# spb_sample_sch.net
KiCad netlist of a schematic drawn in Altium Designer
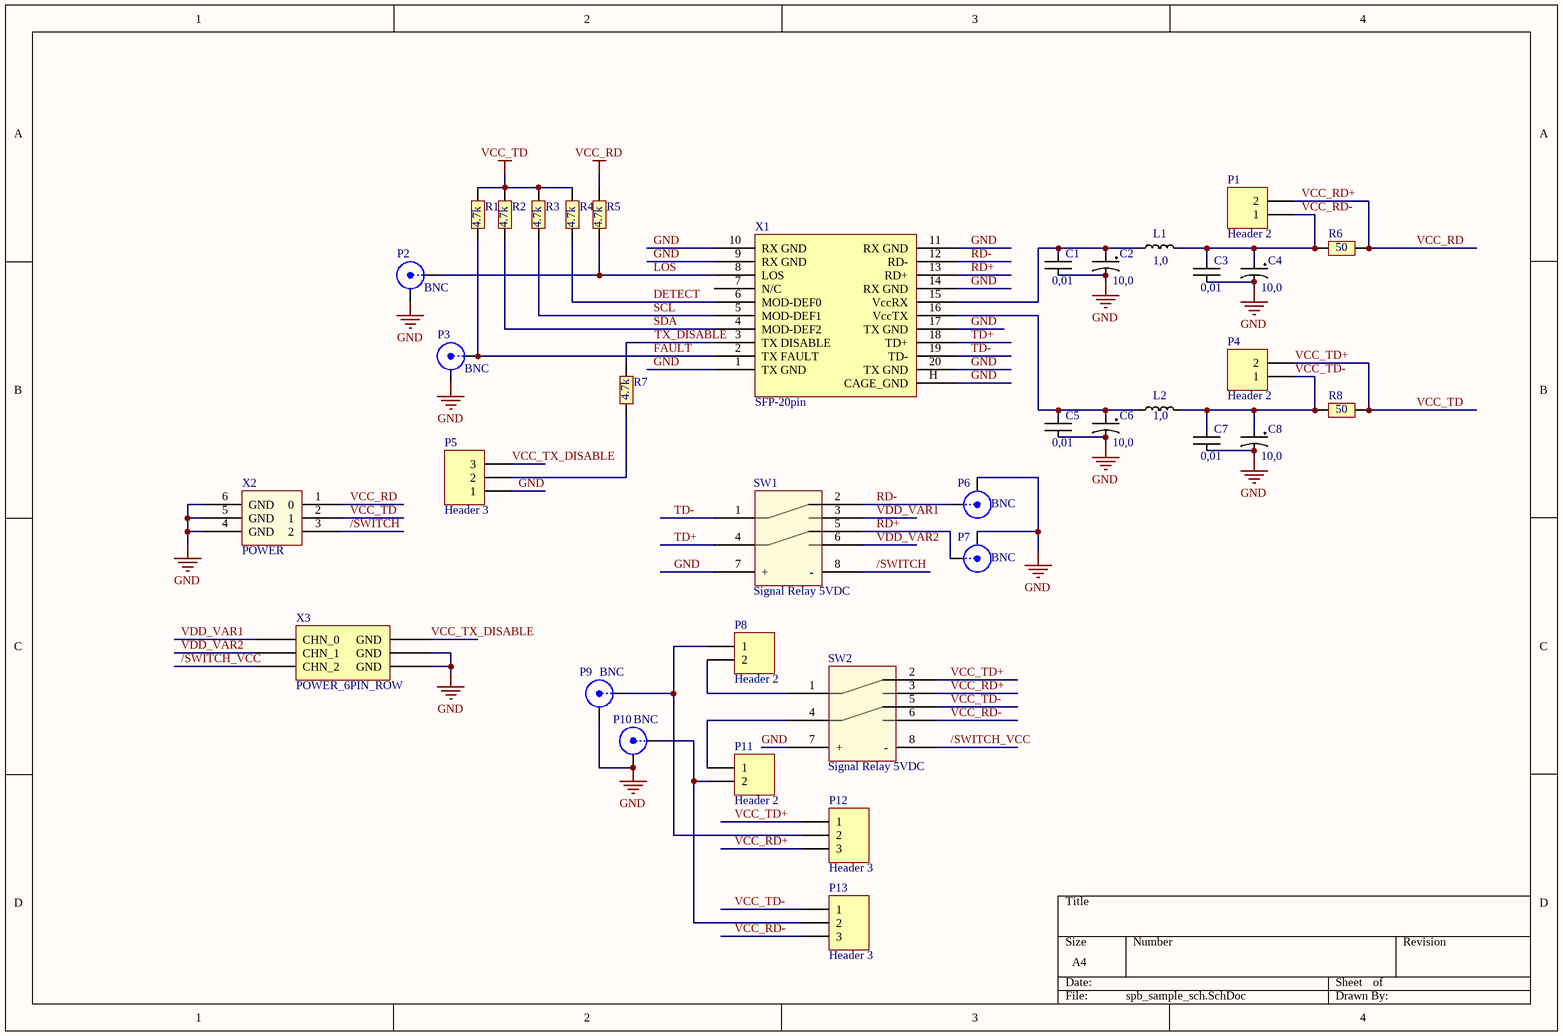
[diagram p0: spb_sample_sch.SchDoc]

(export (version "E")
  (design (tool "Eeschema 10.0.6"))
  (components
    (comp (ref "C1")
      (value "0,01")
      (footprint "0805")
      (description "0805")
      (libsource (lib "MIT_Schlib") (part "CAP_SMALL"))
    )
    (comp (ref "C2")
      (value "10,0")
      (footprint "TYPE_C")
      (description "SMD")
      (libsource (lib "MIT_Schlib") (part "CAP_TANT"))
    )
    (comp (ref "C3")
      (value "0,01")
      (footprint "0805")
      (description "0805")
      (libsource (lib "MIT_Schlib") (part "CAP_SMALL"))
    )
    (comp (ref "C4")
      (value "10,0")
      (footprint "TYPE_C")
      (description "SMD")
      (libsource (lib "MIT_Schlib") (part "CAP_TANT"))
    )
    (comp (ref "C5")
      (value "0,01")
      (footprint "0805")
      (description "0805")
      (libsource (lib "MIT_Schlib") (part "CAP_SMALL"))
    )
    (comp (ref "C6")
      (value "10,0")
      (footprint "TYPE_C")
      (description "SMD")
      (libsource (lib "MIT_Schlib") (part "CAP_TANT"))
    )
    (comp (ref "C7")
      (value "0,01")
      (footprint "0805")
      (description "0805")
      (libsource (lib "MIT_Schlib") (part "CAP_SMALL"))
    )
    (comp (ref "C8")
      (value "10,0")
      (footprint "TYPE_C")
      (description "SMD")
      (libsource (lib "MIT_Schlib") (part "CAP_TANT"))
    )
    (comp (ref "L1")
      (value "1,0")
      (footprint "0805")
      (description "0805")
      (libsource (lib "MIT_Schlib") (part "INDUCT"))
    )
    (comp (ref "L2")
      (value "1,0")
      (footprint "0805")
      (description "0805")
      (libsource (lib "MIT_Schlib") (part "INDUCT"))
    )
    (comp (ref "P1")
      (value "Header 2")
      (footprint "HDR1X2")
      (description "Header, 2-Pin")
      (fields (field (name "PUBLISHER") "Altium Limited"))
      (libsource (lib "Miscellaneous Connectors") (part "Header 2"))
    )
    (comp (ref "P2")
      (value "BNC")
      (footprint "BNC_RA CON")
      (description "BNC Elbow Connector")
      (fields (field (name "PUBLISHER") "Altium Limited"))
      (libsource (lib "Miscellaneous Connectors") (part "BNC"))
    )
    (comp (ref "P3")
      (value "BNC")
      (footprint "BNC_RA CON")
      (description "BNC Elbow Connector")
      (fields (field (name "PUBLISHER") "Altium Limited"))
      (libsource (lib "Miscellaneous Connectors") (part "BNC"))
    )
    (comp (ref "P4")
      (value "Header 2")
      (footprint "HDR1X2")
      (description "Header, 2-Pin")
      (fields (field (name "PUBLISHER") "Altium Limited"))
      (libsource (lib "Miscellaneous Connectors") (part "Header 2"))
    )
    (comp (ref "P5")
      (value "Header 3")
      (footprint "HDR1X3")
      (description "Header, 3-Pin")
      (fields (field (name "PUBLISHER") "Altium Limited"))
      (libsource (lib "") (part "Header 3_1"))
    )
    (comp (ref "P6")
      (value "BNC")
      (footprint "BNC_RA CON")
      (description "BNC Elbow Connector")
      (fields (field (name "PUBLISHER") "Altium Limited"))
      (libsource (lib "Miscellaneous Connectors") (part "BNC"))
    )
    (comp (ref "P7")
      (value "BNC")
      (footprint "BNC_RA CON")
      (description "BNC Elbow Connector")
      (fields (field (name "PUBLISHER") "Altium Limited"))
      (libsource (lib "Miscellaneous Connectors") (part "BNC"))
    )
    (comp (ref "P8")
      (value "Header 2")
      (footprint "HDR1X2")
      (description "Header, 2-Pin")
      (fields (field (name "PUBLISHER") "Altium Limited"))
      (libsource (lib "") (part "Header 2_1"))
    )
    (comp (ref "P9")
      (value "BNC")
      (footprint "BNC_RA CON")
      (description "BNC Elbow Connector")
      (fields (field (name "PUBLISHER") "Altium Limited"))
      (libsource (lib "Miscellaneous Connectors") (part "BNC"))
    )
    (comp (ref "P10")
      (value "BNC")
      (footprint "BNC_RA CON")
      (description "BNC Elbow Connector")
      (fields (field (name "PUBLISHER") "Altium Limited"))
      (libsource (lib "Miscellaneous Connectors") (part "BNC"))
    )
    (comp (ref "P11")
      (value "Header 2")
      (footprint "HDR1X2")
      (description "Header, 2-Pin")
      (fields (field (name "PUBLISHER") "Altium Limited"))
      (libsource (lib "") (part "Header 2_1"))
    )
    (comp (ref "P12")
      (value "Header 3")
      (footprint "HDR1X3")
      (description "Header, 3-Pin")
      (fields (field (name "PUBLISHER") "Altium Limited"))
      (libsource (lib "Miscellaneous Connectors") (part "Header 3"))
    )
    (comp (ref "P13")
      (value "Header 3")
      (footprint "HDR1X3")
      (description "Header, 3-Pin")
      (fields (field (name "PUBLISHER") "Altium Limited"))
      (libsource (lib "Miscellaneous Connectors") (part "Header 3"))
    )
    (comp (ref "R1")
      (value "4.7k")
      (footprint "0805")
      (description "0805")
      (libsource (lib "") (part "RES0805_1"))
    )
    (comp (ref "R2")
      (value "4.7k")
      (footprint "0805")
      (description "0805")
      (libsource (lib "") (part "RES0805_1"))
    )
    (comp (ref "R3")
      (value "4.7k")
      (footprint "0805")
      (description "0805")
      (libsource (lib "") (part "RES0805_1"))
    )
    (comp (ref "R4")
      (value "4.7k")
      (footprint "0805")
      (description "0805")
      (libsource (lib "") (part "RES0805_1"))
    )
    (comp (ref "R5")
      (value "4.7k")
      (footprint "0805")
      (description "0805")
      (libsource (lib "") (part "RES0805_1"))
    )
    (comp (ref "R6")
      (value "50")
      (footprint "0805")
      (description "0805")
      (libsource (lib "MIT_Schlib") (part "RES0805"))
    )
    (comp (ref "R7")
      (value "4.7k")
      (footprint "0805")
      (description "0805")
      (libsource (lib "") (part "RES0805_1"))
    )
    (comp (ref "R8")
      (value "50")
      (footprint "0805")
      (description "0805")
      (libsource (lib "MIT_Schlib") (part "RES0805"))
    )
    (comp (ref "SW1")
      (value "Signal Relay 5VDC")
      (footprint "V23079 Relay")
      (libsource (lib "MIT_Schlib") (part "SWITCH"))
    )
    (comp (ref "SW2")
      (value "Signal Relay 5VDC")
      (footprint "V23079 Relay")
      (libsource (lib "MIT_Schlib") (part "SWITCH"))
    )
    (comp (ref "X1")
      (value "SFP-20pin")
      (footprint "SFP-20pin")
      (libsource (lib "MIT_Schlib") (part "SFP-20pin"))
    )
    (comp (ref "X2") (value "POWER") (footprint "POWER") (libsource (lib "Schlib") (part "POWER")))
    (comp (ref "X3")
      (value "POWER_6PIN_ROW")
      (footprint "POWER_6PIN_ROW")
      (libsource (lib "MIT_Schlib") (part "POWER_6PIN_ROW"))
    )
  )
  (nets
    (net (code "2") (name "/DETECT") (class "Default")
      (node (ref "R4") (pin "2") (pinfunction "2_2") (pintype "passive"))
      (node (ref "X1") (pin "6") (pinfunction "MOD-DEF0_6") (pintype "passive"))
    )
    (net (code "3") (name "/FAULT") (class "Default")
      (node (ref "P3") (pin "1") (pinfunction "X_1") (pintype "passive"))
      (node (ref "R1") (pin "2") (pinfunction "2_2") (pintype "passive"))
      (node (ref "X1") (pin "2") (pinfunction "TX_FAULT_2") (pintype "passive"))
    )
    (net (code "4") (name "/LOS") (class "Default")
      (node (ref "P2") (pin "1") (pinfunction "X_1") (pintype "passive"))
      (node (ref "R5") (pin "2") (pinfunction "2_2") (pintype "passive"))
      (node (ref "X1") (pin "8") (pinfunction "LOS_8") (pintype "passive"))
    )
    (net (code "5") (name "/RD+") (class "Default")
      (node (ref "P7") (pin "1") (pinfunction "X_1") (pintype "passive"))
      (node (ref "SW1") (pin "5") (pinfunction "-_5") (pintype "passive"))
      (node (ref "X1") (pin "13") (pinfunction "RD+_13") (pintype "passive"))
    )
    (net (code "6") (name "/RD-") (class "Default")
      (node (ref "P6") (pin "1") (pinfunction "X_1") (pintype "passive"))
      (node (ref "SW1") (pin "2") (pinfunction "-_2") (pintype "passive"))
      (node (ref "X1") (pin "12") (pinfunction "RD-_12") (pintype "passive"))
    )
    (net (code "7") (name "/SCL") (class "Default")
      (node (ref "R3") (pin "2") (pinfunction "2_2") (pintype "passive"))
      (node (ref "X1") (pin "5") (pinfunction "MOD-DEF1_5") (pintype "passive"))
    )
    (net (code "8") (name "/SDA") (class "Default")
      (node (ref "R2") (pin "2") (pinfunction "2_2") (pintype "passive"))
      (node (ref "X1") (pin "4") (pinfunction "MOD-DEF2_4") (pintype "passive"))
    )
    (net (code "9") (name "/TD+") (class "Default")
      (node (ref "SW1") (pin "4") (pinfunction "-_4") (pintype "passive"))
      (node (ref "X1") (pin "18") (pinfunction "TD+_18") (pintype "passive"))
    )
    (net (code "10") (name "/TD-") (class "Default")
      (node (ref "SW1") (pin "1") (pinfunction "-_1") (pintype "passive"))
      (node (ref "X1") (pin "19") (pinfunction "TD-_19") (pintype "passive"))
    )
    (net (code "11") (name "/TX_DISABLE") (class "Default")
      (node (ref "R7") (pin "1") (pinfunction "1_1") (pintype "passive"))
      (node (ref "X1") (pin "3") (pinfunction "TX_DISABLE_3") (pintype "passive"))
    )
    (net (code "12") (name "/VCC_RD-") (class "Default")
      (node (ref "C3") (pin "1") (pinfunction "1_1") (pintype "passive"))
      (node (ref "C4") (pin "2") (pinfunction "2_2") (pintype "passive"))
      (node (ref "L1") (pin "2") (pinfunction "2_2") (pintype "passive"))
      (node (ref "P1") (pin "1") (pinfunction "1_1") (pintype "passive"))
      (node (ref "P13") (pin "3") (pinfunction "3_3") (pintype "passive"))
      (node (ref "R6") (pin "1") (pinfunction "1_1") (pintype "passive"))
      (node (ref "SW2") (pin "6") (pinfunction "-_6") (pintype "passive"))
    )
    (net (code "13") (name "/VCC_TD-") (class "Default")
      (node (ref "C7") (pin "1") (pinfunction "1_1") (pintype "passive"))
      (node (ref "C8") (pin "2") (pinfunction "2_2") (pintype "passive"))
      (node (ref "L2") (pin "2") (pinfunction "2_2") (pintype "passive"))
      (node (ref "P13") (pin "1") (pinfunction "1_1") (pintype "passive"))
      (node (ref "P4") (pin "1") (pinfunction "1_1") (pintype "passive"))
      (node (ref "R8") (pin "1") (pinfunction "1_1") (pintype "passive"))
      (node (ref "SW2") (pin "5") (pinfunction "-_5") (pintype "passive"))
    )
    (net (code "14") (name "/VCC_TX_DISABLE") (class "Default")
      (node (ref "P5") (pin "3") (pinfunction "3_3") (pintype "passive"))
      (node (ref "X3") (pin "2") (pinfunction "GND_2") (pintype "passive"))
    )
    (net (code "15") (name "/VDD_VAR1") (class "Default")
      (node (ref "SW1") (pin "3") (pinfunction "-_3") (pintype "passive"))
      (node (ref "X3") (pin "1") (pinfunction "CHN_0_1") (pintype "passive"))
    )
    (net (code "16") (name "/VDD_VAR2") (class "Default")
      (node (ref "SW1") (pin "6") (pinfunction "-_6") (pintype "passive"))
      (node (ref "X3") (pin "3") (pinfunction "CHN_1_3") (pintype "passive"))
    )
    (net (code "17") (name "/{slash}SWITCH") (class "Default")
      (node (ref "SW1") (pin "8") (pinfunction "-_8") (pintype "passive"))
      (node (ref "X2") (pin "3") (pinfunction "2_3") (pintype "passive"))
    )
    (net (code "18") (name "/{slash}SWITCH_VCC") (class "Default")
      (node (ref "SW2") (pin "8") (pinfunction "-_8") (pintype "passive"))
      (node (ref "X3") (pin "6") (pinfunction "CHN_2_6") (pintype "passive"))
    )
    (net (code "19") (name "GND") (class "Default")
      (node (ref "C1") (pin "2") (pinfunction "2_2") (pintype "passive"))
      (node (ref "C2") (pin "1") (pinfunction "1_1") (pintype "passive"))
      (node (ref "C3") (pin "2") (pinfunction "2_2") (pintype "passive"))
      (node (ref "C4") (pin "1") (pinfunction "1_1") (pintype "passive"))
      (node (ref "C5") (pin "2") (pinfunction "2_2") (pintype "passive"))
      (node (ref "C6") (pin "1") (pinfunction "1_1") (pintype "passive"))
      (node (ref "C7") (pin "2") (pinfunction "2_2") (pintype "passive"))
      (node (ref "C8") (pin "1") (pinfunction "1_1") (pintype "passive"))
      (node (ref "P10") (pin "2") (pinfunction "Y_2") (pintype "passive"))
      (node (ref "P2") (pin "2") (pinfunction "Y_2") (pintype "passive"))
      (node (ref "P3") (pin "2") (pinfunction "Y_2") (pintype "passive"))
      (node (ref "P5") (pin "1") (pinfunction "1_1") (pintype "passive"))
      (node (ref "P6") (pin "2") (pinfunction "Y_2") (pintype "passive"))
      (node (ref "P7") (pin "2") (pinfunction "Y_2") (pintype "passive"))
      (node (ref "P9") (pin "2") (pinfunction "Y_2") (pintype "passive"))
      (node (ref "SW1") (pin "7") (pinfunction "+_7") (pintype "passive"))
      (node (ref "SW2") (pin "7") (pinfunction "+_7") (pintype "passive"))
      (node (ref "X1") (pin "1") (pinfunction "TX_GND_1") (pintype "passive"))
      (node (ref "X1") (pin "10") (pinfunction "RX_GND_10") (pintype "passive"))
      (node (ref "X1") (pin "11") (pinfunction "RX_GND_11") (pintype "passive"))
      (node (ref "X1") (pin "14") (pinfunction "RX_GND_14") (pintype "passive"))
      (node (ref "X1") (pin "17") (pinfunction "TX_GND_17") (pintype "passive"))
      (node (ref "X1") (pin "20") (pinfunction "TX_GND_20") (pintype "passive"))
      (node (ref "X1") (pin "9") (pinfunction "RX_GND_9") (pintype "passive"))
      (node (ref "X1") (pin "H") (pinfunction "CAGE_GND_H") (pintype "passive"))
      (node (ref "X2") (pin "4") (pinfunction "GND_4") (pintype "passive"))
      (node (ref "X2") (pin "5") (pinfunction "GND_5") (pintype "passive"))
      (node (ref "X2") (pin "6") (pinfunction "GND_6") (pintype "passive"))
      (node (ref "X3") (pin "4") (pinfunction "GND_4") (pintype "passive"))
      (node (ref "X3") (pin "5") (pinfunction "GND_5") (pintype "passive"))
    )
    (net (code "20") (name "Net-(P5-Pad2)") (class "Default")
      (node (ref "P5") (pin "2") (pinfunction "2_2") (pintype "passive"))
      (node (ref "R7") (pin "2") (pinfunction "2_2") (pintype "passive"))
    )
    (net (code "21") (name "Net-(P8-Pad2)") (class "Default")
      (node (ref "P8") (pin "2") (pinfunction "2_2") (pintype "passive"))
      (node (ref "SW2") (pin "1") (pinfunction "-_1") (pintype "passive"))
    )
    (net (code "22") (name "Net-(P9-X)") (class "Default")
      (node (ref "P12") (pin "2") (pinfunction "2_2") (pintype "passive"))
      (node (ref "P8") (pin "1") (pinfunction "1_1") (pintype "passive"))
      (node (ref "P9") (pin "1") (pinfunction "X_1") (pintype "passive"))
    )
    (net (code "23") (name "Net-(P10-X)") (class "Default")
      (node (ref "P10") (pin "1") (pinfunction "X_1") (pintype "passive"))
      (node (ref "P11") (pin "2") (pinfunction "2_2") (pintype "passive"))
      (node (ref "P13") (pin "2") (pinfunction "2_2") (pintype "passive"))
    )
    (net (code "24") (name "Net-(P11-Pad1)") (class "Default")
      (node (ref "P11") (pin "1") (pinfunction "1_1") (pintype "passive"))
      (node (ref "SW2") (pin "4") (pinfunction "-_4") (pintype "passive"))
    )
    (net (code "25") (name "Net-(X1-VccRX)") (class "Default")
      (node (ref "C1") (pin "1") (pinfunction "1_1") (pintype "passive"))
      (node (ref "C2") (pin "2") (pinfunction "2_2") (pintype "passive"))
      (node (ref "L1") (pin "1") (pinfunction "1_1") (pintype "passive"))
      (node (ref "X1") (pin "15") (pinfunction "VccRX_15") (pintype "passive"))
    )
    (net (code "26") (name "Net-(X1-VccTX)") (class "Default")
      (node (ref "C5") (pin "1") (pinfunction "1_1") (pintype "passive"))
      (node (ref "C6") (pin "2") (pinfunction "2_2") (pintype "passive"))
      (node (ref "L2") (pin "1") (pinfunction "1_1") (pintype "passive"))
      (node (ref "X1") (pin "16") (pinfunction "VccTX_16") (pintype "passive"))
    )
    (net (code "27") (name "VCC_RD") (class "Default")
      (node (ref "P1") (pin "2") (pinfunction "2_2") (pintype "passive"))
      (node (ref "P12") (pin "3") (pinfunction "3_3") (pintype "passive"))
      (node (ref "R5") (pin "1") (pinfunction "1_1") (pintype "passive"))
      (node (ref "R6") (pin "2") (pinfunction "2_2") (pintype "passive"))
      (node (ref "SW2") (pin "3") (pinfunction "-_3") (pintype "passive"))
      (node (ref "X2") (pin "1") (pinfunction "0_1") (pintype "passive"))
    )
    (net (code "28") (name "VCC_TD") (class "Default")
      (node (ref "P12") (pin "1") (pinfunction "1_1") (pintype "passive"))
      (node (ref "P4") (pin "2") (pinfunction "2_2") (pintype "passive"))
      (node (ref "R1") (pin "1") (pinfunction "1_1") (pintype "passive"))
      (node (ref "R2") (pin "1") (pinfunction "1_1") (pintype "passive"))
      (node (ref "R3") (pin "1") (pinfunction "1_1") (pintype "passive"))
      (node (ref "R4") (pin "1") (pinfunction "1_1") (pintype "passive"))
      (node (ref "R8") (pin "2") (pinfunction "2_2") (pintype "passive"))
      (node (ref "SW2") (pin "2") (pinfunction "-_2") (pintype "passive"))
      (node (ref "X2") (pin "2") (pinfunction "1_2") (pintype "passive"))
    )
    (net (code "29") (name "unconnected-(X1-N{slash}C-Pad7)") (class "Default")
      (node (ref "X1") (pin "7") (pinfunction "N/C_7") (pintype "passive"))
    )
  )
)
